# NMT_RS_232.net
KiCad netlist of a schematic drawn in Altium Designer
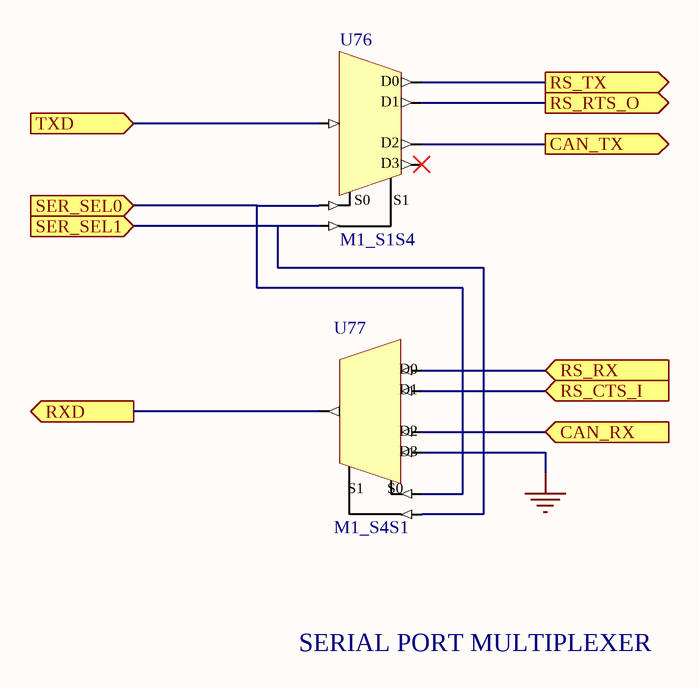
[diagram p0: NMT_RS_232.SCHDOC]

(export (version "E")
  (design (tool "Eeschema 10.0.6"))
  (components
    (comp (ref "U76")
      (value "M1_S1S4")
      (description "1x1-Single Wire to 4x1-Single Wire Multiplexer (Demultiplex)")
      (fields (field (name "PUBLISHER") "Altium Limited"))
      (libsource (lib "FPGA Generic") (part "M1_S1S4"))
    )
    (comp (ref "U77")
      (value "M1_S4S1")
      (description "4x1-Single Wire to 1x1-Single Wire Multiplexer")
      (fields (field (name "PUBLISHER") "Altium Limited"))
      (libsource (lib "FPGA Generic") (part "M1_S4S1"))
    )
  )
  (nets
    (net (code "1") (name "/CAN_RX") (class "Default")
      (node (ref "U77") (pin "D2") (pinfunction "D2_D2") (pintype "input"))
    )
    (net (code "2") (name "/CAN_TX") (class "Default")
      (node (ref "U76") (pin "D2") (pinfunction "D2_D2") (pintype "output"))
    )
    (net (code "3") (name "/RS_CTS_I") (class "Default")
      (node (ref "U77") (pin "D1") (pinfunction "D1_D1") (pintype "input"))
    )
    (net (code "4") (name "/RS_RTS_O") (class "Default")
      (node (ref "U76") (pin "D1") (pinfunction "D1_D1") (pintype "output"))
    )
    (net (code "5") (name "/RS_RX") (class "Default")
      (node (ref "U77") (pin "D0") (pinfunction "D0_D0") (pintype "input"))
    )
    (net (code "6") (name "/RS_TX") (class "Default")
      (node (ref "U76") (pin "D0") (pinfunction "D0_D0") (pintype "output"))
    )
    (net (code "7") (name "/RXD") (class "Default")
      (node (ref "U77") (pin "O") (pinfunction "O_O") (pintype "output"))
    )
    (net (code "8") (name "/SER_SEL0") (class "Default")
      (node (ref "U76") (pin "S0") (pinfunction "S0_S0") (pintype "input"))
      (node (ref "U77") (pin "S0") (pinfunction "S0_S0") (pintype "input"))
    )
    (net (code "9") (name "/SER_SEL1") (class "Default")
      (node (ref "U76") (pin "S1") (pinfunction "S1_S1") (pintype "input"))
      (node (ref "U77") (pin "S1") (pinfunction "S1_S1") (pintype "input"))
    )
    (net (code "10") (name "/TXD") (class "Default")
      (node (ref "U76") (pin "O") (pinfunction "O_O") (pintype "input"))
    )
    (net (code "11") (name "GND") (class "Default")
      (node (ref "U77") (pin "D3") (pinfunction "D3_D3") (pintype "input"))
    )
    (net (code "12") (name "unconnected-(U76-PadD3)") (class "Default")
      (node (ref "U76") (pin "D3") (pinfunction "D3_D3") (pintype "output+no_connect"))
    )
  )
)
